# Microcontroller.net
KiCad netlist of a schematic drawn in Altium Designer
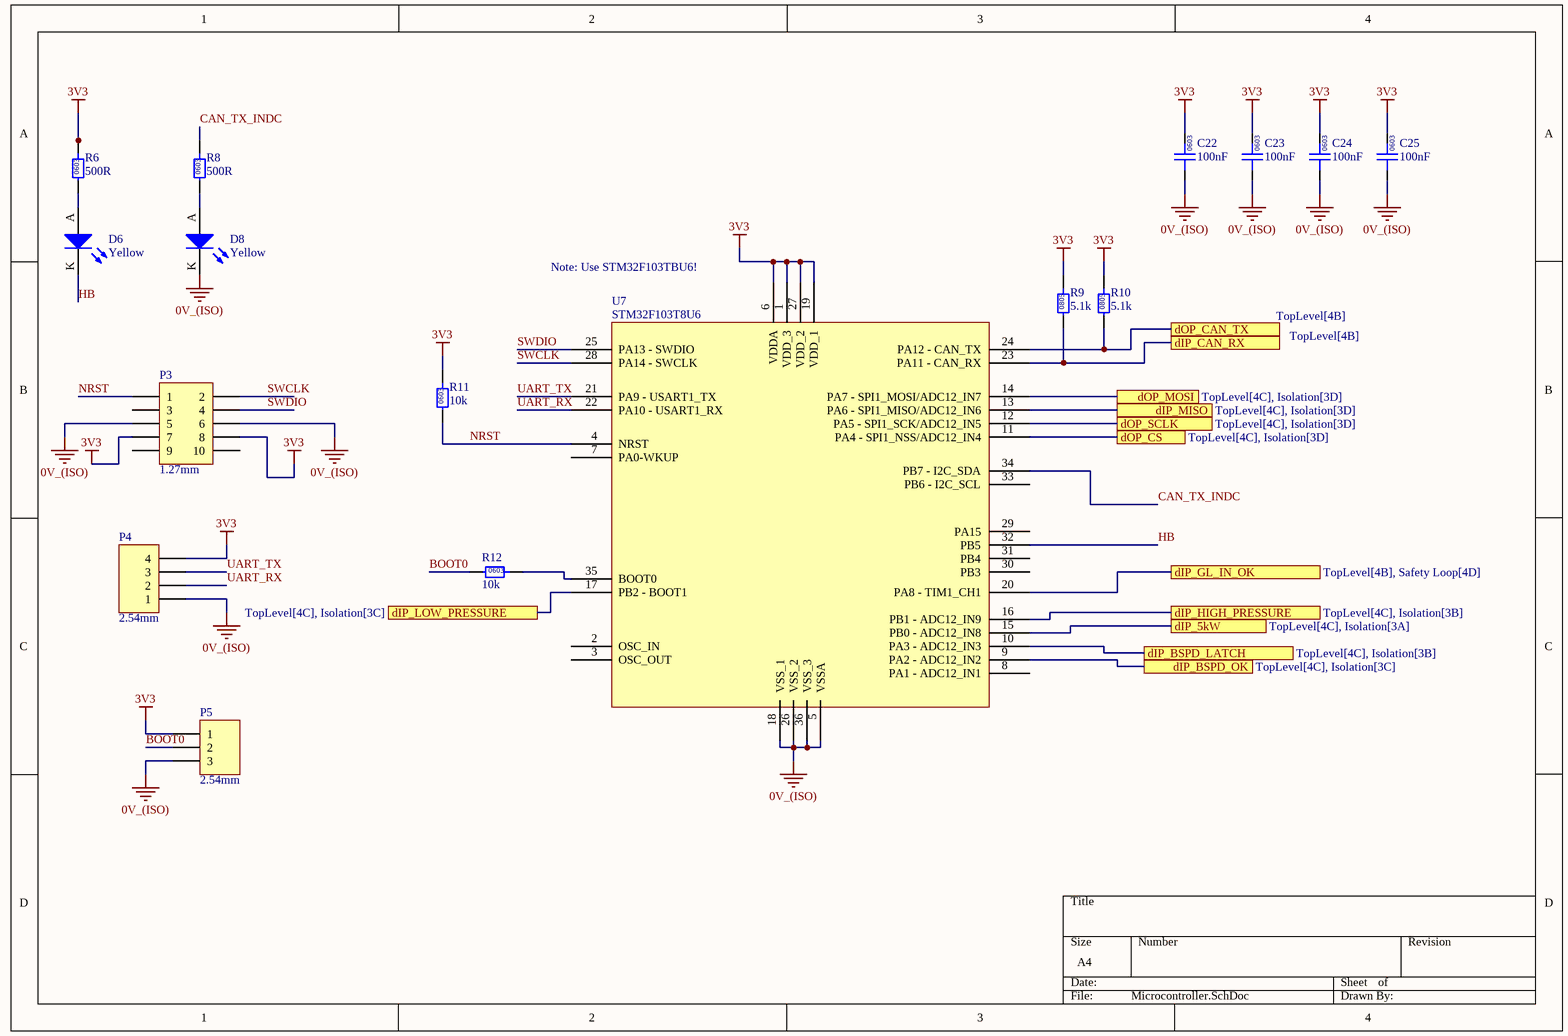
[diagram p0: Microcontroller.SchDoc]

(export (version "E")
  (design (tool "Eeschema 10.0.6"))
  (components
    (comp (ref "C22")
      (value "100nF")
      (footprint "0603")
      (fields
        (field (name "PART NUMBER") "GCM188L81H104KA57D")
        (field (name "MANUFACTURER") "muRata")
        (field (name "TOLERANCE") "±10%")
      )
      (libsource (lib "ts_standard_library") (part "Capacitor 0603"))
    )
    (comp (ref "C23")
      (value "100nF")
      (footprint "0603")
      (fields
        (field (name "PART NUMBER") "GCM188L81H104KA57D")
        (field (name "MANUFACTURER") "muRata")
        (field (name "TOLERANCE") "±10%")
      )
      (libsource (lib "ts_standard_library") (part "Capacitor 0603"))
    )
    (comp (ref "C24")
      (value "100nF")
      (footprint "0603")
      (fields
        (field (name "PART NUMBER") "GCM188L81H104KA57D")
        (field (name "MANUFACTURER") "muRata")
        (field (name "TOLERANCE") "±10%")
      )
      (libsource (lib "ts_standard_library") (part "Capacitor 0603"))
    )
    (comp (ref "C25")
      (value "100nF")
      (footprint "0603")
      (fields
        (field (name "PART NUMBER") "GCM188L81H104KA57D")
        (field (name "MANUFACTURER") "muRata")
        (field (name "TOLERANCE") "±10%")
      )
      (libsource (lib "ts_standard_library") (part "Capacitor 0603"))
    )
    (comp (ref "D6")
      (value "Yellow")
      (footprint "0805 LED")
      (description "Yellow LED Indication - Discrete 1.75V 0805 (2012 Metric)")
      (fields (field (name "PART NUMBER") "SML-211YTT86") (field (name "MANUFACTURER") "ROHM Semiconductor"))
      (libsource (lib "ts_standard_library") (part "LED"))
    )
    (comp (ref "D8")
      (value "Yellow")
      (footprint "0805 LED")
      (description "Yellow LED Indication - Discrete 1.75V 0805 (2012 Metric)")
      (fields (field (name "PART NUMBER") "SML-211YTT86") (field (name "MANUFACTURER") "ROHM Semiconductor"))
      (libsource (lib "ts_standard_library") (part "LED"))
    )
    (comp (ref "P3")
      (value "1.27mm")
      (footprint "3221-10-0300-00")
      (fields
        (field (name "PART NUMBER") "SMD 1.27mm Header 2x5 (3221-10-0300-00)")
        (field (name "CONTACT") "NA")
      )
      (libsource (lib "ts_standard_connectors") (part "Header 2x5"))
    )
    (comp (ref "P4")
      (value "2.54mm")
      (footprint "TH 2.54mm Header 1x4")
      (fields (field (name "PART NUMBER") "TH 2.54mm Header 1x4") (field (name "CONTACT") "NA"))
      (libsource (lib "ts_standard_connectors") (part "Header 1x4"))
    )
    (comp (ref "P5")
      (value "2.54mm")
      (footprint "TH 2.54mm Header 1x3")
      (fields (field (name "PART NUMBER") "TH 2.54mm Header 1x3") (field (name "CONTACT") "NA"))
      (libsource (lib "ts_standard_connectors") (part "Header 1x3"))
    )
    (comp (ref "R6")
      (value "500R")
      (footprint "0603")
      (fields
        (field (name "PART NUMBER") "RT0603BRD07500RL")
        (field (name "MANUFACTURER") "YAGEO")
        (field (name "TOLERANCE") "0.01")
      )
      (libsource (lib "ts_standard_library") (part "Resistor 0603"))
    )
    (comp (ref "R8")
      (value "500R")
      (footprint "0603")
      (fields
        (field (name "PART NUMBER") "RT0603BRD07500RL")
        (field (name "MANUFACTURER") "YAGEO")
        (field (name "TOLERANCE") "0.01")
      )
      (libsource (lib "ts_standard_library") (part "Resistor 0603"))
    )
    (comp (ref "R9")
      (value "5.1k")
      (footprint "0805")
      (fields
        (field (name "PART NUMBER") "RC0805FR075K1L")
        (field (name "MANUFACTURER") "YAGEO")
        (field (name "TOLERANCE") "0.01")
      )
      (libsource (lib "ts_standard_library") (part "Resistor 0805"))
    )
    (comp (ref "R10")
      (value "5.1k")
      (footprint "0805")
      (fields
        (field (name "PART NUMBER") "RC0805FR075K1L")
        (field (name "MANUFACTURER") "YAGEO")
        (field (name "TOLERANCE") "0.01")
      )
      (libsource (lib "ts_standard_library") (part "Resistor 0805"))
    )
    (comp (ref "R11")
      (value "10k")
      (footprint "0603")
      (fields
        (field (name "PART NUMBER") "RC0603FR-0710KL")
        (field (name "MANUFACTURER") "YAGEO")
        (field (name "TOLERANCE") "0.01")
      )
      (libsource (lib "ts_standard_library") (part "Resistor 0603"))
    )
    (comp (ref "R12")
      (value "10k")
      (footprint "0603")
      (fields
        (field (name "PART NUMBER") "RC0603FR-0710KL")
        (field (name "MANUFACTURER") "YAGEO")
        (field (name "TOLERANCE") "0.01")
      )
      (libsource (lib "ts_standard_library") (part "Resistor 0603"))
    )
    (comp (ref "U7")
      (value "STM32F103T8U6")
      (footprint "STM_QFN-36")
      (description "ARM® Cortex®-M3 STM32F1 Microcontroller IC 32-Bit 72MHz 64KB (64K x 8) FLASH QFN")
      (fields (field (name "MANUFACTURER") "ST Microelectronics"))
      (libsource (lib "ts_standard_library") (part "STM32F103T8U6"))
    )
  )
  (nets
    (net (code "1") (name "/BOOT0") (class "Default")
      (node (ref "P5") (pin "2") (pinfunction "2_2") (pintype "passive"))
      (node (ref "R12") (pin "1") (pinfunction "1_1") (pintype "passive"))
    )
    (net (code "2") (name "/CAN_TX_INDC") (class "Default")
      (node (ref "R8") (pin "2") (pinfunction "2_2") (pintype "passive"))
      (node (ref "U7") (pin "34") (pinfunction "PB7_-_I2C_SDA_34") (pintype "passive"))
    )
    (net (code "3") (name "/HB") (class "Default")
      (node (ref "D6") (pin "K") (pinfunction "K_K") (pintype "passive"))
      (node (ref "U7") (pin "32") (pinfunction "PB5_32") (pintype "passive"))
    )
    (net (code "4") (name "/NRST") (class "Default")
      (node (ref "P3") (pin "1") (pinfunction "1_1") (pintype "passive"))
      (node (ref "R11") (pin "1") (pinfunction "1_1") (pintype "passive"))
      (node (ref "U7") (pin "4") (pinfunction "NRST_4") (pintype "passive"))
    )
    (net (code "5") (name "/SWCLK") (class "Default")
      (node (ref "P3") (pin "2") (pinfunction "2_2") (pintype "passive"))
      (node (ref "U7") (pin "28") (pinfunction "PA14_-_SWCLK_28") (pintype "passive"))
    )
    (net (code "6") (name "/SWDIO") (class "Default")
      (node (ref "P3") (pin "4") (pinfunction "4_4") (pintype "passive"))
      (node (ref "U7") (pin "25") (pinfunction "PA13_-_SWDIO_25") (pintype "passive"))
    )
    (net (code "7") (name "/UART_RX") (class "Default")
      (node (ref "P4") (pin "2") (pinfunction "2_2") (pintype "passive"))
      (node (ref "U7") (pin "22") (pinfunction "PA10_-_USART1_RX_22") (pintype "passive"))
    )
    (net (code "8") (name "/UART_TX") (class "Default")
      (node (ref "P4") (pin "3") (pinfunction "3_3") (pintype "passive"))
      (node (ref "U7") (pin "21") (pinfunction "PA9_-_USART1_TX_21") (pintype "passive"))
    )
    (net (code "9") (name "/dIP_5kW") (class "Default")
      (node (ref "U7") (pin "15") (pinfunction "PB0_-_ADC12_IN8_15") (pintype "passive"))
    )
    (net (code "10") (name "/dIP_BSPD_LATCH") (class "Default")
      (node (ref "U7") (pin "10") (pinfunction "PA3_-_ADC12_IN3_10") (pintype "passive"))
    )
    (net (code "11") (name "/dIP_BSPD_OK") (class "Default")
      (node (ref "U7") (pin "9") (pinfunction "PA2_-_ADC12_IN2_9") (pintype "passive"))
    )
    (net (code "12") (name "/dIP_CAN_RX") (class "Default")
      (node (ref "R9") (pin "1") (pinfunction "1_1") (pintype "passive"))
      (node (ref "U7") (pin "23") (pinfunction "PA11_-_CAN_RX_23") (pintype "passive"))
    )
    (net (code "13") (name "/dIP_GL_IN_OK") (class "Default")
      (node (ref "U7") (pin "20") (pinfunction "PA8_-_TIM1_CH1_20") (pintype "passive"))
    )
    (net (code "14") (name "/dIP_HIGH_PRESSURE") (class "Default")
      (node (ref "U7") (pin "16") (pinfunction "PB1_-_ADC12_IN9_16") (pintype "passive"))
    )
    (net (code "15") (name "/dIP_LOW_PRESSURE") (class "Default")
      (node (ref "U7") (pin "17") (pinfunction "PB2_-_BOOT1_17") (pintype "passive"))
    )
    (net (code "16") (name "/dIP_MISO") (class "Default")
      (node (ref "U7") (pin "13") (pinfunction "PA6_-_SPI1_MISO/ADC12_IN6_13") (pintype "passive"))
    )
    (net (code "17") (name "/dOP_CAN_TX") (class "Default")
      (node (ref "R10") (pin "1") (pinfunction "1_1") (pintype "passive"))
      (node (ref "U7") (pin "24") (pinfunction "PA12_-_CAN_TX_24") (pintype "passive"))
    )
    (net (code "18") (name "/dOP_CS") (class "Default")
      (node (ref "U7") (pin "11") (pinfunction "PA4_-_SPI1_NSS/ADC12_IN4_11") (pintype "passive"))
    )
    (net (code "19") (name "/dOP_MOSI") (class "Default")
      (node (ref "U7") (pin "14") (pinfunction "PA7_-_SPI1_MOSI/ADC12_IN7_14") (pintype "passive"))
    )
    (net (code "20") (name "/dOP_SCLK") (class "Default")
      (node (ref "U7") (pin "12") (pinfunction "PA5_-_SPI1_SCK/ADC12_IN5_12") (pintype "passive"))
    )
    (net (code "21") (name "0V_(ISO)") (class "Default")
      (node (ref "C22") (pin "1") (pinfunction "1_1") (pintype "passive"))
      (node (ref "C23") (pin "1") (pinfunction "1_1") (pintype "passive"))
      (node (ref "C24") (pin "1") (pinfunction "1_1") (pintype "passive"))
      (node (ref "C25") (pin "1") (pinfunction "1_1") (pintype "passive"))
      (node (ref "D8") (pin "K") (pinfunction "K_K") (pintype "passive"))
      (node (ref "P3") (pin "5") (pinfunction "5_5") (pintype "passive"))
      (node (ref "P3") (pin "6") (pinfunction "6_6") (pintype "passive"))
      (node (ref "P4") (pin "1") (pinfunction "1_1") (pintype "passive"))
      (node (ref "P5") (pin "3") (pinfunction "3_3") (pintype "passive"))
      (node (ref "U7") (pin "18") (pinfunction "VSS_1_18") (pintype "passive"))
      (node (ref "U7") (pin "26") (pinfunction "VSS_2_26") (pintype "passive"))
      (node (ref "U7") (pin "36") (pinfunction "VSS_3_36") (pintype "passive"))
      (node (ref "U7") (pin "5") (pinfunction "VSSA_5") (pintype "passive"))
    )
    (net (code "22") (name "3V3") (class "Default")
      (node (ref "C22") (pin "2") (pinfunction "2_2") (pintype "passive"))
      (node (ref "C23") (pin "2") (pinfunction "2_2") (pintype "passive"))
      (node (ref "C24") (pin "2") (pinfunction "2_2") (pintype "passive"))
      (node (ref "C25") (pin "2") (pinfunction "2_2") (pintype "passive"))
      (node (ref "P3") (pin "7") (pinfunction "7_7") (pintype "passive"))
      (node (ref "P3") (pin "8") (pinfunction "8_8") (pintype "passive"))
      (node (ref "P4") (pin "4") (pinfunction "4_4") (pintype "passive"))
      (node (ref "P5") (pin "1") (pinfunction "1_1") (pintype "passive"))
      (node (ref "R10") (pin "2") (pinfunction "2_2") (pintype "passive"))
      (node (ref "R11") (pin "2") (pinfunction "2_2") (pintype "passive"))
      (node (ref "R6") (pin "2") (pinfunction "2_2") (pintype "passive"))
      (node (ref "R9") (pin "2") (pinfunction "2_2") (pintype "passive"))
      (node (ref "U7") (pin "1") (pinfunction "VDD_3_1") (pintype "passive"))
      (node (ref "U7") (pin "19") (pinfunction "VDD_1_19") (pintype "passive"))
      (node (ref "U7") (pin "27") (pinfunction "VDD_2_27") (pintype "passive"))
      (node (ref "U7") (pin "6") (pinfunction "VDDA_6") (pintype "passive"))
    )
    (net (code "23") (name "Net-(D6-PadA)") (class "Default")
      (node (ref "D6") (pin "A") (pinfunction "A_A") (pintype "passive"))
      (node (ref "R6") (pin "1") (pinfunction "1_1") (pintype "passive"))
    )
    (net (code "24") (name "Net-(D8-PadA)") (class "Default")
      (node (ref "D8") (pin "A") (pinfunction "A_A") (pintype "passive"))
      (node (ref "R8") (pin "1") (pinfunction "1_1") (pintype "passive"))
    )
    (net (code "25") (name "Net-(U7-BOOT0)") (class "Default")
      (node (ref "R12") (pin "2") (pinfunction "2_2") (pintype "passive"))
      (node (ref "U7") (pin "35") (pinfunction "BOOT0_35") (pintype "passive"))
    )
    (net (code "26") (name "unconnected-(P3-Pad3)") (class "Default")
      (node (ref "P3") (pin "3") (pinfunction "3_3") (pintype "passive"))
    )
    (net (code "27") (name "unconnected-(P3-Pad9)") (class "Default")
      (node (ref "P3") (pin "9") (pinfunction "9_9") (pintype "passive"))
    )
    (net (code "28") (name "unconnected-(P3-Pad10)") (class "Default")
      (node (ref "P3") (pin "10") (pinfunction "10_10") (pintype "passive"))
    )
    (net (code "29") (name "unconnected-(U7-OSC_IN-Pad2)") (class "Default")
      (node (ref "U7") (pin "2") (pinfunction "OSC_IN_2") (pintype "passive"))
    )
    (net (code "30") (name "unconnected-(U7-OSC_OUT-Pad3)") (class "Default")
      (node (ref "U7") (pin "3") (pinfunction "OSC_OUT_3") (pintype "passive"))
    )
    (net (code "31") (name "unconnected-(U7-PA0-WKUP-Pad7)") (class "Default")
      (node (ref "U7") (pin "7") (pinfunction "PA0-WKUP_7") (pintype "passive"))
    )
    (net (code "32") (name "unconnected-(U7-PA1_-_ADC12_IN1-Pad8)") (class "Default")
      (node (ref "U7") (pin "8") (pinfunction "PA1_-_ADC12_IN1_8") (pintype "passive"))
    )
    (net (code "33") (name "unconnected-(U7-PA15-Pad29)") (class "Default")
      (node (ref "U7") (pin "29") (pinfunction "PA15_29") (pintype "passive"))
    )
    (net (code "34") (name "unconnected-(U7-PB3-Pad30)") (class "Default")
      (node (ref "U7") (pin "30") (pinfunction "PB3_30") (pintype "passive"))
    )
    (net (code "35") (name "unconnected-(U7-PB4-Pad31)") (class "Default")
      (node (ref "U7") (pin "31") (pinfunction "PB4_31") (pintype "passive"))
    )
    (net (code "36") (name "unconnected-(U7-PB6_-_I2C_SCL-Pad33)") (class "Default")
      (node (ref "U7") (pin "33") (pinfunction "PB6_-_I2C_SCL_33") (pintype "passive"))
    )
  )
)
